# COMMS.net
KiCad netlist of a schematic drawn in Altium Designer
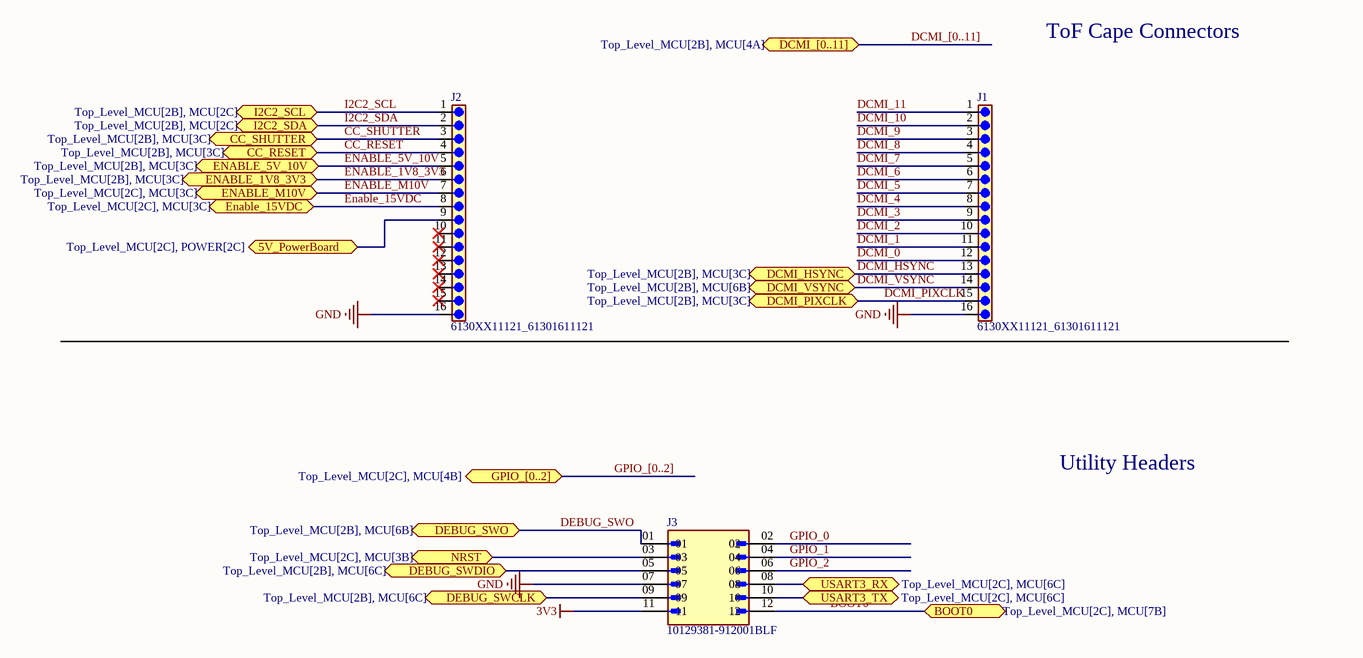
[diagram p0: COMMS.SchDoc]

(export (version "E")
  (design (tool "Eeschema 10.0.6"))
  (components
    (comp (ref "J1")
      (value "6130XX11121_61301611121")
      (footprint "61301611121")
      (fields (field (name "MF") "{'manufacturer': u'Wurth Electronics'}") (field (name "MP") "61301611121"))
      (libsource (lib "6130XX11121_61301611121") (part "6130XX11121_61301611121"))
    )
    (comp (ref "J2")
      (value "6130XX11121_61301611121")
      (footprint "61301611121")
      (fields (field (name "MF") "{'manufacturer': u'Wurth Electronics'}") (field (name "MP") "61301611121"))
      (libsource (lib "6130XX11121_61301611121") (part "6130XX11121_61301611121"))
    )
    (comp (ref "J3")
      (value "10129381-912001BLF")
      (footprint "AMPHENOL_10129381-912001BLF")
      (fields
        (field (name "MF") "Amphenol ICC (FCI)")
        (field (name "DIGI-KEY_PART_NUMBER") "10129381-912001BLF-ND")
      )
      (libsource (lib "10129381-912001BLF") (part "10129381-912001BLF"))
    )
  )
  (nets
    (net (code "1") (name "/5V_PowerBoard") (class "Default")
      (node (ref "J2") (pin "9") (pinfunction "9_9") (pintype "passive"))
    )
    (net (code "2") (name "/BOOT0") (class "Default")
      (node (ref "J3") (pin "12") (pinfunction "12_12") (pintype "passive"))
    )
    (net (code "3") (name "/CC_RESET") (class "Default")
      (node (ref "J2") (pin "4") (pinfunction "4_4") (pintype "passive"))
    )
    (net (code "4") (name "/CC_SHUTTER") (class "Default")
      (node (ref "J2") (pin "3") (pinfunction "3_3") (pintype "passive"))
    )
    (net (code "5") (name "/DCMI_0") (class "Default")
      (node (ref "J1") (pin "12") (pinfunction "12_12") (pintype "passive"))
    )
    (net (code "6") (name "/DCMI_1") (class "Default")
      (node (ref "J1") (pin "11") (pinfunction "11_11") (pintype "passive"))
    )
    (net (code "7") (name "/DCMI_2") (class "Default")
      (node (ref "J1") (pin "10") (pinfunction "10_10") (pintype "passive"))
    )
    (net (code "8") (name "/DCMI_3") (class "Default")
      (node (ref "J1") (pin "9") (pinfunction "9_9") (pintype "passive"))
    )
    (net (code "9") (name "/DCMI_4") (class "Default")
      (node (ref "J1") (pin "8") (pinfunction "8_8") (pintype "passive"))
    )
    (net (code "10") (name "/DCMI_5") (class "Default")
      (node (ref "J1") (pin "7") (pinfunction "7_7") (pintype "passive"))
    )
    (net (code "11") (name "/DCMI_6") (class "Default")
      (node (ref "J1") (pin "6") (pinfunction "6_6") (pintype "passive"))
    )
    (net (code "12") (name "/DCMI_7") (class "Default")
      (node (ref "J1") (pin "5") (pinfunction "5_5") (pintype "passive"))
    )
    (net (code "13") (name "/DCMI_8") (class "Default")
      (node (ref "J1") (pin "4") (pinfunction "4_4") (pintype "passive"))
    )
    (net (code "14") (name "/DCMI_9") (class "Default")
      (node (ref "J1") (pin "3") (pinfunction "3_3") (pintype "passive"))
    )
    (net (code "15") (name "/DCMI_10") (class "Default")
      (node (ref "J1") (pin "2") (pinfunction "2_2") (pintype "passive"))
    )
    (net (code "16") (name "/DCMI_11") (class "Default")
      (node (ref "J1") (pin "1") (pinfunction "1_1") (pintype "passive"))
    )
    (net (code "17") (name "/DCMI_HSYNC") (class "Default")
      (node (ref "J1") (pin "13") (pinfunction "13_13") (pintype "passive"))
    )
    (net (code "18") (name "/DCMI_PIXCLK") (class "Default")
      (node (ref "J1") (pin "15") (pinfunction "15_15") (pintype "passive"))
    )
    (net (code "19") (name "/DCMI_VSYNC") (class "Default")
      (node (ref "J1") (pin "14") (pinfunction "14_14") (pintype "passive"))
    )
    (net (code "21") (name "/DEBUG_SWCLK") (class "Default")
      (node (ref "J3") (pin "09") (pinfunction "09_09") (pintype "passive"))
    )
    (net (code "22") (name "/DEBUG_SWDIO") (class "Default")
      (node (ref "J3") (pin "05") (pinfunction "05_05") (pintype "passive"))
    )
    (net (code "23") (name "/DEBUG_SWO") (class "Default")
      (node (ref "J3") (pin "01") (pinfunction "01_01") (pintype "passive"))
    )
    (net (code "24") (name "/ENABLE_1V8_3V3") (class "Default")
      (node (ref "J2") (pin "6") (pinfunction "6_6") (pintype "passive"))
    )
    (net (code "25") (name "/ENABLE_5V_10V") (class "Default")
      (node (ref "J2") (pin "5") (pinfunction "5_5") (pintype "passive"))
    )
    (net (code "26") (name "/ENABLE_M10V") (class "Default")
      (node (ref "J2") (pin "7") (pinfunction "7_7") (pintype "passive"))
    )
    (net (code "27") (name "/Enable_15VDC") (class "Default")
      (node (ref "J2") (pin "8") (pinfunction "8_8") (pintype "passive"))
    )
    (net (code "28") (name "/GPIO_0") (class "Default")
      (node (ref "J3") (pin "02") (pinfunction "02_02") (pintype "passive"))
    )
    (net (code "29") (name "/GPIO_1") (class "Default")
      (node (ref "J3") (pin "04") (pinfunction "04_04") (pintype "passive"))
    )
    (net (code "30") (name "/GPIO_2") (class "Default")
      (node (ref "J3") (pin "06") (pinfunction "06_06") (pintype "passive"))
    )
    (net (code "32") (name "/I2C2_SCL") (class "Default")
      (node (ref "J2") (pin "1") (pinfunction "1_1") (pintype "passive"))
    )
    (net (code "33") (name "/I2C2_SDA") (class "Default")
      (node (ref "J2") (pin "2") (pinfunction "2_2") (pintype "passive"))
    )
    (net (code "34") (name "/NRST") (class "Default")
      (node (ref "J3") (pin "03") (pinfunction "03_03") (pintype "passive"))
    )
    (net (code "35") (name "/USART3_RX") (class "Default")
      (node (ref "J3") (pin "08") (pinfunction "08_08") (pintype "passive"))
    )
    (net (code "36") (name "/USART3_TX") (class "Default")
      (node (ref "J3") (pin "10") (pinfunction "10_10") (pintype "passive"))
    )
    (net (code "37") (name "3V3") (class "Default")
      (node (ref "J3") (pin "11") (pinfunction "11_11") (pintype "passive"))
    )
    (net (code "38") (name "GND") (class "Default")
      (node (ref "J1") (pin "16") (pinfunction "16_16") (pintype "passive"))
      (node (ref "J2") (pin "16") (pinfunction "16_16") (pintype "passive"))
      (node (ref "J3") (pin "07") (pinfunction "07_07") (pintype "passive"))
    )
    (net (code "39") (name "unconnected-(J2-Pad10)") (class "Default")
      (node (ref "J2") (pin "10") (pinfunction "10_10") (pintype "passive+no_connect"))
    )
    (net (code "40") (name "unconnected-(J2-Pad11)") (class "Default")
      (node (ref "J2") (pin "11") (pinfunction "11_11") (pintype "passive+no_connect"))
    )
    (net (code "41") (name "unconnected-(J2-Pad12)") (class "Default")
      (node (ref "J2") (pin "12") (pinfunction "12_12") (pintype "passive+no_connect"))
    )
    (net (code "42") (name "unconnected-(J2-Pad13)") (class "Default")
      (node (ref "J2") (pin "13") (pinfunction "13_13") (pintype "passive+no_connect"))
    )
    (net (code "43") (name "unconnected-(J2-Pad14)") (class "Default")
      (node (ref "J2") (pin "14") (pinfunction "14_14") (pintype "passive+no_connect"))
    )
    (net (code "44") (name "unconnected-(J2-Pad15)") (class "Default")
      (node (ref "J2") (pin "15") (pinfunction "15_15") (pintype "passive+no_connect"))
    )
  )
)
